# Receiver_1_5.net
KiCad netlist of a schematic drawn in Altium Designer
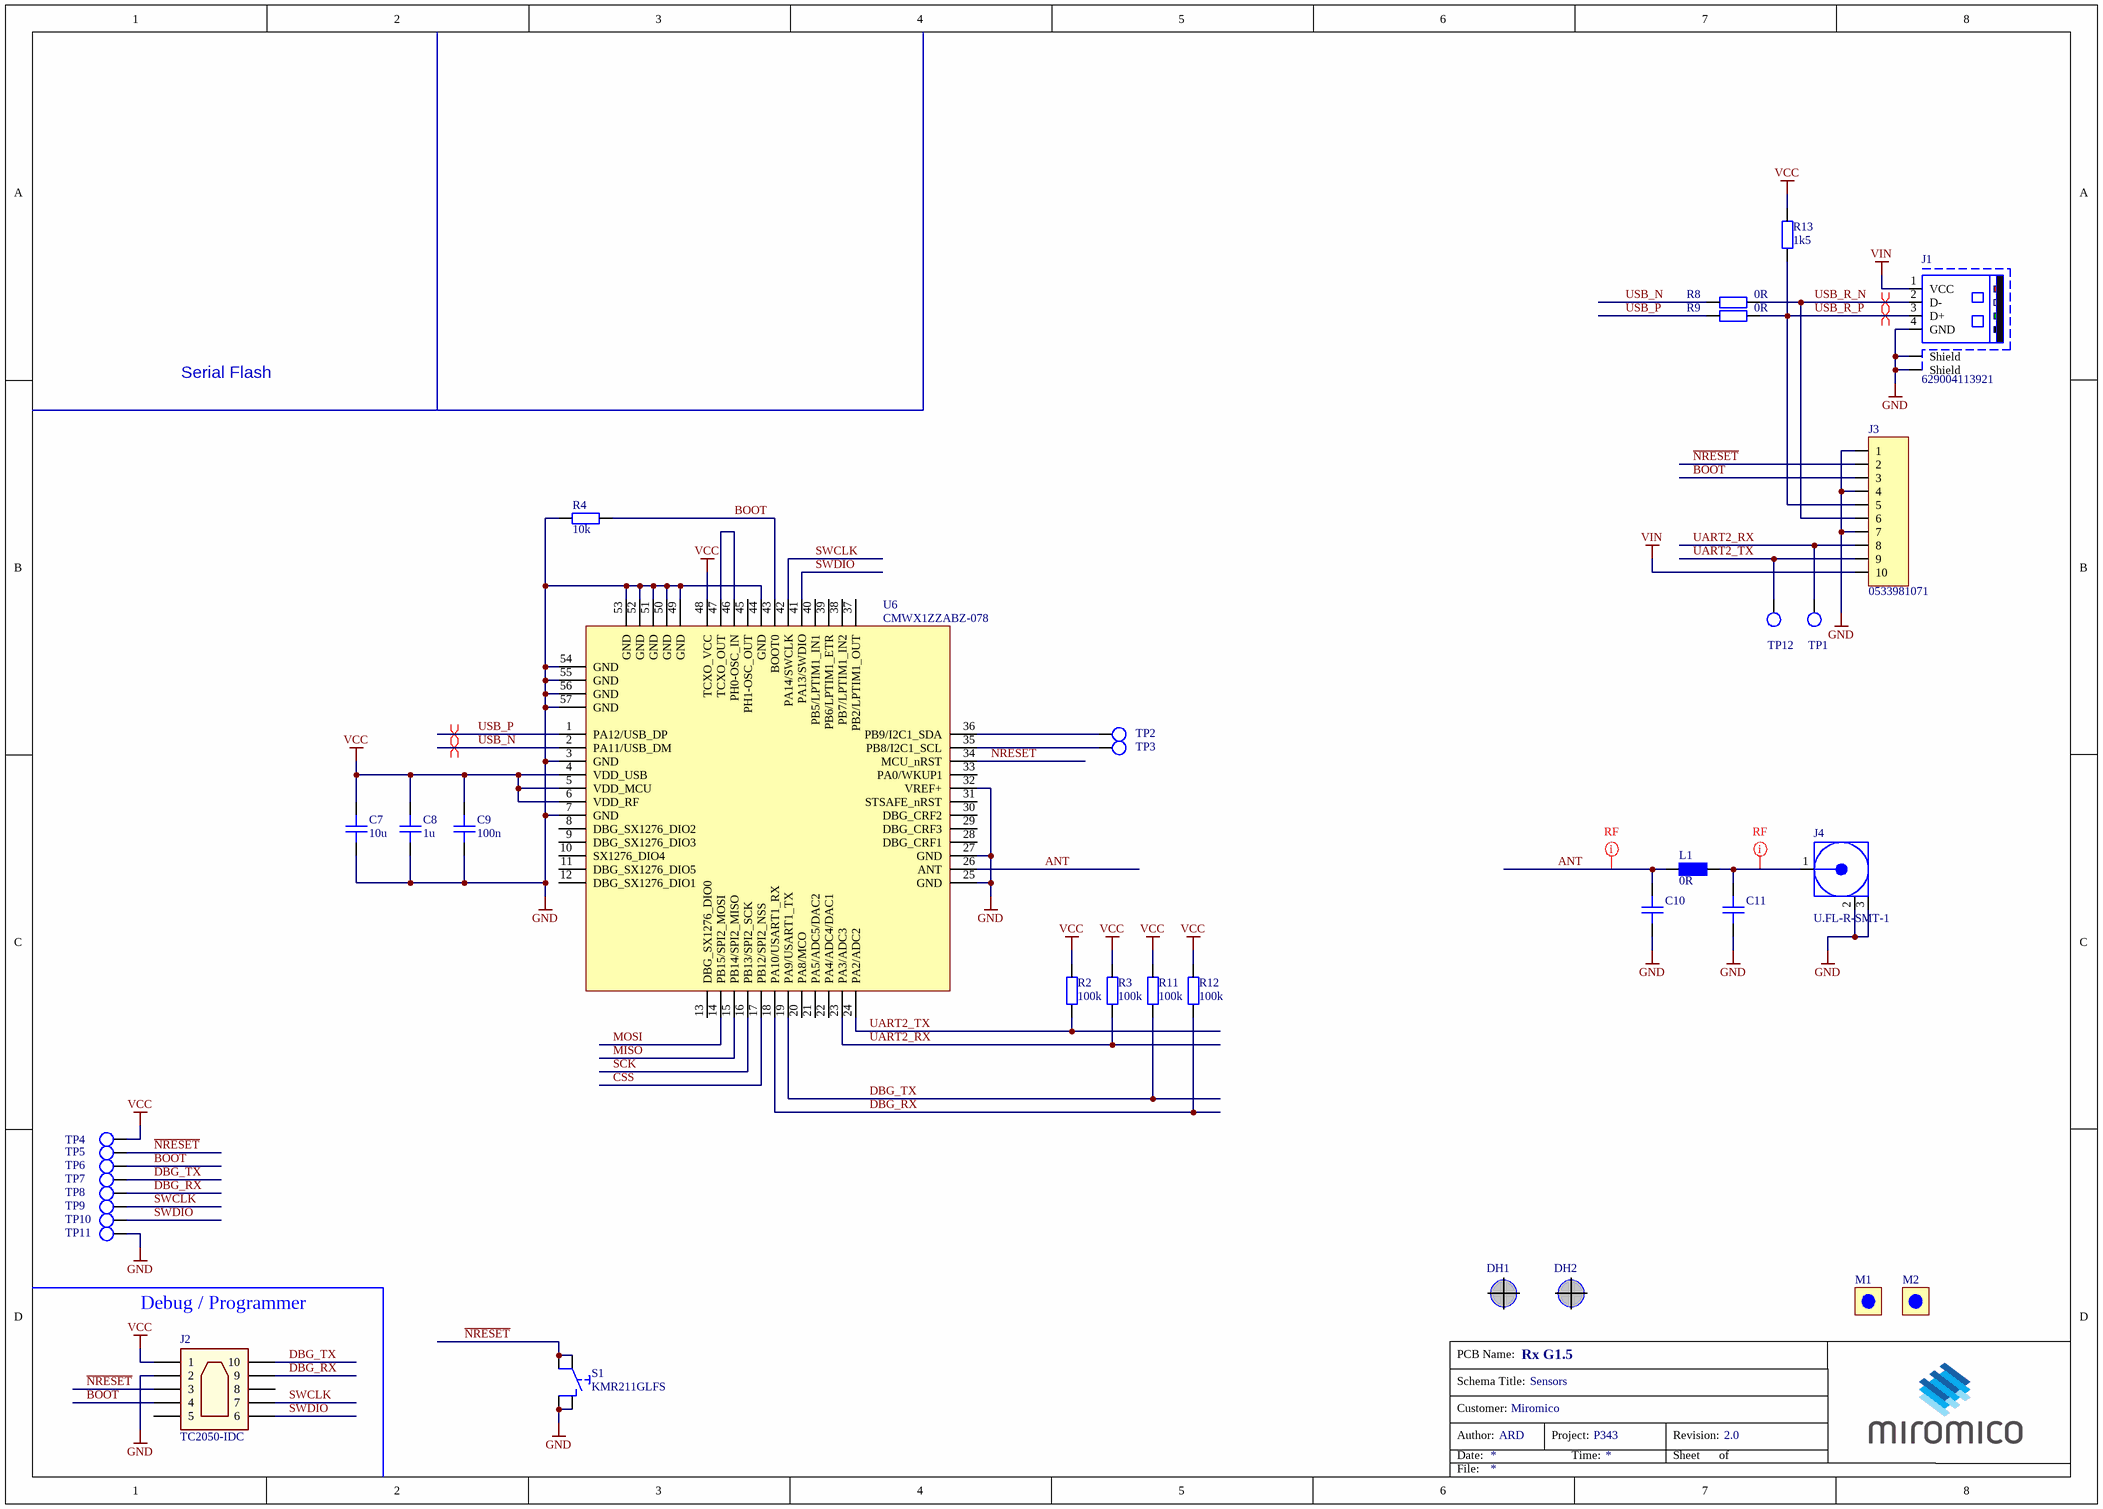
[diagram p0: Receiver_1_5.SchDoc]

(export (version "E")
  (design (tool "Eeschema 10.0.6"))
  (components
    (comp (ref "C7")
      (value "10u")
      (footprint "CAPC0402(1005)60_L")
      (description "Chip Capacitor")
      (libsource (lib "Altium Vault Miromico") (part "C_Chip"))
    )
    (comp (ref "C8")
      (value "1u")
      (footprint "CAPC0402(1005)60_L")
      (description "Chip Capacitor")
      (libsource (lib "Altium Vault Miromico") (part "C_Chip"))
    )
    (comp (ref "C9")
      (value "100n")
      (footprint "CAPC0402(1005)60_L")
      (description "Chip Capacitor")
      (libsource (lib "Altium Vault Miromico") (part "C_Chip"))
    )
    (comp (ref "C10")
      (value "~")
      (footprint "CAPC0402(1005)60_L")
      (description "Chip Capacitor")
      (fields
        (field (name "MANUFACTURER") "Murata Electronics North America")
        (field (name "TOLERANCE") "±0.1pF")
      )
      (libsource (lib "Altium Vault Miromico") (part "C_Chip-03"))
    )
    (comp (ref "C11")
      (value "~")
      (footprint "CAPC0402(1005)60_L")
      (description "Chip Capacitor")
      (fields
        (field (name "MANUFACTURER") "Murata Electronics North America")
        (field (name "TOLERANCE") "±0.1pF")
      )
      (libsource (lib "Altium Vault Miromico") (part "C_Chip-03"))
    )
    (comp (ref "DH1")
      (value "Drill hole M2.5_nonplated")
      (footprint "Drill hole M2.5_nonplated")
      (libsource (lib "Altium Vault Miromico") (part "Drill hole M2.5_nonplated-01"))
    )
    (comp (ref "DH2")
      (value "Drill hole M2.5_nonplated")
      (footprint "Drill hole M2.5_nonplated")
      (libsource (lib "Altium Vault Miromico") (part "Drill hole M2.5_nonplated-01"))
    )
    (comp (ref "J1")
      (value "629004113921")
      (footprint "629004113921")
      (description "WR-COM USB Type A SMT with Clip")
      (fields (field (name "MANUFACTURER") "Wurth Electronics Inc"))
      (libsource (lib "Altium Vault Miromico") (part "629004113921-01"))
    )
    (comp (ref "J2")
      (value "TC2050-IDC")
      (footprint "TC2050-IDC-NL-10")
      (description "TDC2050-IDC, 10Pins, dual footprint (leg and no-legs)")
      (fields (field (name "MANUFACTURER") "Tag-Connect"))
      (libsource (lib "Altium Vault Miromico") (part "TDC2050-IDC-01"))
    )
    (comp (ref "J3")
      (value "0533981071")
      (footprint "0533981071")
      (description "CONN HEADER 10POS 1.25MM VRT SMD")
      (fields (field (name "MANUFACTURER") "Molex, LLC"))
      (libsource (lib "Altium Vault Miromico") (part "0533981071"))
    )
    (comp (ref "J4")
      (value "U.FL-R-SMT-1")
      (footprint "U.FL")
      (description "Ultra Small Surface Mount Coaxial Connectors")
      (fields
        (field (name "MANUFACTURER") "Hirose Electric Co Ltd")
        (field (name "PLACETEC PART NUMBER") "182-916100000000")
      )
      (libsource (lib "Connectors") (part "COAX - U.FL-R-SMT-1"))
    )
    (comp (ref "L1")
      (value "0R")
      (footprint "L_0402_HF")
      (description "Chip Inductor")
      (fields (field (name "TOLERANCE") "±1%"))
      (libsource (lib "Altium Vault Miromico") (part "L_Chip_0402_HF-01"))
    )
    (comp (ref "M1")
      (value "Fiducial Round")
      (footprint "Fiducial round_small")
      (description "Fiducial (Optical Marker)")
      (libsource (lib "Altium Vault Miromico") (part "Fiducial Round-04"))
    )
    (comp (ref "M2")
      (value "Fiducial Round")
      (footprint "Fiducial round_small")
      (description "Fiducial (Optical Marker)")
      (libsource (lib "Altium Vault Miromico") (part "Fiducial Round-04"))
    )
    (comp (ref "R2")
      (value "100k")
      (footprint "RESC0402(1005)_L")
      (description "Chip Resistor")
      (libsource (lib "Altium Vault Miromico") (part "R_Chip"))
    )
    (comp (ref "R3")
      (value "100k")
      (footprint "RESC0402(1005)_L")
      (description "Chip Resistor")
      (libsource (lib "Altium Vault Miromico") (part "R_Chip"))
    )
    (comp (ref "R4")
      (value "10k")
      (footprint "RESC0402(1005)_L")
      (description "Chip Resistor")
      (libsource (lib "") (part "R_Chip-05_1"))
    )
    (comp (ref "R8")
      (value "0R")
      (footprint "RESC0402(1005)_L")
      (description "Chip Resistor")
      (libsource (lib "Altium Vault Miromico") (part "R_Chip-05"))
    )
    (comp (ref "R9")
      (value "0R")
      (footprint "RESC0402(1005)_L")
      (description "Chip Resistor")
      (libsource (lib "Altium Vault Miromico") (part "R_Chip-05"))
    )
    (comp (ref "R11")
      (value "100k")
      (footprint "RESC0402(1005)_L")
      (description "Chip Resistor")
      (libsource (lib "Altium Vault Miromico") (part "R_Chip"))
    )
    (comp (ref "R12")
      (value "100k")
      (footprint "RESC0402(1005)_L")
      (description "Chip Resistor")
      (libsource (lib "Altium Vault Miromico") (part "R_Chip"))
    )
    (comp (ref "R13")
      (value "1k5")
      (footprint "RESC0402(1005)_L")
      (description "Chip Resistor")
      (libsource (lib "Altium Vault Miromico") (part "R_Chip-02"))
    )
    (comp (ref "S1")
      (value "KMR211GLFS")
      (footprint "KMR211GLFS")
      (description "SWITCH TACTILE SPST-NO 0.05A 32V")
      (fields (field (name "MANUFACTURER") "C&K Components"))
      (libsource (lib "Altium Vault Miromico") (part "KMR211GLFS-01"))
    )
    (comp (ref "TP1")
      (value "Testpoint 1.5mm")
      (footprint "Testpoint SMD 1.5mm")
      (description "Testpoint SMD 1.5mm")
      (libsource (lib "Altium Vault Miromico") (part "Testpoint SMD 1.5mm-02"))
    )
    (comp (ref "TP2")
      (value "Testpoint 1.5mm")
      (footprint "Testpoint SMD 1.5mm")
      (description "Testpoint SMD 1.5mm")
      (libsource (lib "Altium Vault Miromico") (part "Testpoint SMD 1.5mm-02"))
    )
    (comp (ref "TP3")
      (value "Testpoint 1.5mm")
      (footprint "Testpoint SMD 1.5mm")
      (description "Testpoint SMD 1.5mm")
      (libsource (lib "Altium Vault Miromico") (part "Testpoint SMD 1.5mm-02"))
    )
    (comp (ref "TP4")
      (value "Testpoint 1.5mm")
      (footprint "Testpoint SMD 1.5mm")
      (description "Testpoint SMD 1.5mm")
      (libsource (lib "Altium Vault Miromico") (part "Testpoint SMD 1.5mm-02"))
    )
    (comp (ref "TP5")
      (value "Testpoint 1.5mm")
      (footprint "Testpoint SMD 1.5mm")
      (description "Testpoint SMD 1.5mm")
      (libsource (lib "Altium Vault Miromico") (part "Testpoint SMD 1.5mm-02"))
    )
    (comp (ref "TP6")
      (value "Testpoint 1.5mm")
      (footprint "Testpoint SMD 1.5mm")
      (description "Testpoint SMD 1.5mm")
      (libsource (lib "Altium Vault Miromico") (part "Testpoint SMD 1.5mm-02"))
    )
    (comp (ref "TP7")
      (value "Testpoint 1.5mm")
      (footprint "Testpoint SMD 1.5mm")
      (description "Testpoint SMD 1.5mm")
      (libsource (lib "Altium Vault Miromico") (part "Testpoint SMD 1.5mm-02"))
    )
    (comp (ref "TP8")
      (value "Testpoint 1.5mm")
      (footprint "Testpoint SMD 1.5mm")
      (description "Testpoint SMD 1.5mm")
      (libsource (lib "Altium Vault Miromico") (part "Testpoint SMD 1.5mm-02"))
    )
    (comp (ref "TP9")
      (value "Testpoint 1.5mm")
      (footprint "Testpoint SMD 1.5mm")
      (description "Testpoint SMD 1.5mm")
      (libsource (lib "Altium Vault Miromico") (part "Testpoint SMD 1.5mm-02"))
    )
    (comp (ref "TP10")
      (value "Testpoint 1.5mm")
      (footprint "Testpoint SMD 1.5mm")
      (description "Testpoint SMD 1.5mm")
      (libsource (lib "Altium Vault Miromico") (part "Testpoint SMD 1.5mm-02"))
    )
    (comp (ref "TP11")
      (value "Testpoint 1.5mm")
      (footprint "Testpoint SMD 1.5mm")
      (description "Testpoint SMD 1.5mm")
      (libsource (lib "Altium Vault Miromico") (part "Testpoint SMD 1.5mm-02"))
    )
    (comp (ref "TP12")
      (value "Testpoint 1.5mm")
      (footprint "Testpoint SMD 1.5mm")
      (description "Testpoint SMD 1.5mm")
      (libsource (lib "Altium Vault Miromico") (part "Testpoint SMD 1.5mm-02"))
    )
    (comp (ref "U6")
      (value "CMWX1ZZABZ-078")
      (footprint "CMWX1ZZABZ")
      (description "LORA MODULE")
      (fields (field (name "MANUFACTURER") "Murata Electronics North America"))
      (libsource (lib "CMWX1ZZABZ") (part "CMWX1ZZABZ-078"))
    )
  )
  (nets
    (net (code "1") (name "/ANT") (class "Default")
      (node (ref "C10") (pin "1") (pinfunction "1_1") (pintype "passive"))
      (node (ref "L1") (pin "2") (pinfunction "2_2") (pintype "passive"))
      (node (ref "U6") (pin "26") (pinfunction "ANT_26") (pintype "passive"))
    )
    (net (code "2") (name "/BOOT") (class "Default")
      (node (ref "J2") (pin "4") (pinfunction "4_4") (pintype "passive"))
      (node (ref "J3") (pin "3") (pinfunction "3_3") (pintype "passive"))
      (node (ref "R4") (pin "1") (pinfunction "1_1") (pintype "passive"))
      (node (ref "TP6") (pin "1") (pinfunction "1_1") (pintype "passive"))
      (node (ref "U6") (pin "43") (pinfunction "BOOT0_43") (pintype "passive"))
    )
    (net (code "3") (name "/CSS") (class "Default")
      (node (ref "U6") (pin "17") (pinfunction "PB12/SPI2_NSS_17") (pintype "passive"))
    )
    (net (code "4") (name "/DBG_RX") (class "Default")
      (node (ref "J2") (pin "9") (pinfunction "9_9") (pintype "passive"))
      (node (ref "R12") (pin "2") (pinfunction "2_2") (pintype "passive"))
      (node (ref "TP8") (pin "1") (pinfunction "1_1") (pintype "passive"))
      (node (ref "U6") (pin "18") (pinfunction "PA10/USART1_RX_18") (pintype "passive"))
    )
    (net (code "5") (name "/DBG_TX") (class "Default")
      (node (ref "J2") (pin "10") (pinfunction "10_10") (pintype "passive"))
      (node (ref "R11") (pin "2") (pinfunction "2_2") (pintype "passive"))
      (node (ref "TP7") (pin "1") (pinfunction "1_1") (pintype "passive"))
      (node (ref "U6") (pin "19") (pinfunction "PA9/USART1_TX_19") (pintype "passive"))
    )
    (net (code "6") (name "/MISO") (class "Default")
      (node (ref "U6") (pin "15") (pinfunction "PB14/SPI2_MISO_15") (pintype "passive"))
    )
    (net (code "7") (name "/MOSI") (class "Default")
      (node (ref "U6") (pin "14") (pinfunction "PB15/SPI2_MOSI_14") (pintype "passive"))
    )
    (net (code "8") (name "/NRESET") (class "Default")
      (node (ref "J2") (pin "3") (pinfunction "3_3") (pintype "passive"))
      (node (ref "J3") (pin "2") (pinfunction "2_2") (pintype "passive"))
      (node (ref "S1") (pin "1") (pinfunction "1_1") (pintype "passive"))
      (node (ref "S1") (pin "2") (pinfunction "2_2") (pintype "passive"))
      (node (ref "TP5") (pin "1") (pinfunction "1_1") (pintype "passive"))
      (node (ref "U6") (pin "34") (pinfunction "MCU_nRST_34") (pintype "passive"))
    )
    (net (code "9") (name "/SCK") (class "Default")
      (node (ref "U6") (pin "16") (pinfunction "PB13/SPI2_SCK_16") (pintype "passive"))
    )
    (net (code "10") (name "/SWCLK") (class "Default")
      (node (ref "J2") (pin "7") (pinfunction "7_7") (pintype "passive"))
      (node (ref "TP9") (pin "1") (pinfunction "1_1") (pintype "passive"))
      (node (ref "U6") (pin "42") (pinfunction "PA14/SWCLK_42") (pintype "passive"))
    )
    (net (code "11") (name "/SWDIO") (class "Default")
      (node (ref "J2") (pin "6") (pinfunction "6_6") (pintype "passive"))
      (node (ref "TP10") (pin "1") (pinfunction "1_1") (pintype "passive"))
      (node (ref "U6") (pin "41") (pinfunction "PA13/SWDIO_41") (pintype "passive"))
    )
    (net (code "12") (name "/UART2_RX") (class "Default")
      (node (ref "J3") (pin "8") (pinfunction "8_8") (pintype "passive"))
      (node (ref "R3") (pin "2") (pinfunction "2_2") (pintype "passive"))
      (node (ref "TP1") (pin "1") (pinfunction "1_1") (pintype "passive"))
      (node (ref "U6") (pin "23") (pinfunction "PA3/ADC3_23") (pintype "passive"))
    )
    (net (code "13") (name "/UART2_TX") (class "Default")
      (node (ref "J3") (pin "9") (pinfunction "9_9") (pintype "passive"))
      (node (ref "R2") (pin "2") (pinfunction "2_2") (pintype "passive"))
      (node (ref "TP12") (pin "1") (pinfunction "1_1") (pintype "passive"))
      (node (ref "U6") (pin "24") (pinfunction "PA2/ADC2_24") (pintype "passive"))
    )
    (net (code "14") (name "/USB_N") (class "Default")
      (node (ref "R8") (pin "1") (pinfunction "1_1") (pintype "passive"))
      (node (ref "U6") (pin "2") (pinfunction "PA11/USB_DM_2") (pintype "passive"))
    )
    (net (code "15") (name "/USB_P") (class "Default")
      (node (ref "R9") (pin "1") (pinfunction "1_1") (pintype "passive"))
      (node (ref "U6") (pin "1") (pinfunction "PA12/USB_DP_1") (pintype "passive"))
    )
    (net (code "16") (name "/USB_R_N") (class "Default")
      (node (ref "J1") (pin "2") (pinfunction "D-_2") (pintype "passive"))
      (node (ref "J3") (pin "6") (pinfunction "6_6") (pintype "passive"))
      (node (ref "R8") (pin "2") (pinfunction "2_2") (pintype "passive"))
    )
    (net (code "17") (name "/USB_R_P") (class "Default")
      (node (ref "J1") (pin "3") (pinfunction "D+_3") (pintype "passive"))
      (node (ref "J3") (pin "5") (pinfunction "5_5") (pintype "passive"))
      (node (ref "R13") (pin "2") (pinfunction "2_2") (pintype "passive"))
      (node (ref "R9") (pin "2") (pinfunction "2_2") (pintype "passive"))
    )
    (net (code "18") (name "GND") (class "Default")
      (node (ref "C10") (pin "2") (pinfunction "2_2") (pintype "passive"))
      (node (ref "C11") (pin "2") (pinfunction "2_2") (pintype "passive"))
      (node (ref "C7") (pin "1") (pinfunction "1_1") (pintype "passive"))
      (node (ref "C8") (pin "1") (pinfunction "1_1") (pintype "passive"))
      (node (ref "C9") (pin "1") (pinfunction "1_1") (pintype "passive"))
      (node (ref "J1") (pin "4") (pinfunction "GND_4") (pintype "passive"))
      (node (ref "J1") (pin "Z1") (pinfunction "Shield_Z1") (pintype "passive"))
      (node (ref "J1") (pin "Z2") (pinfunction "Shield_Z2") (pintype "passive"))
      (node (ref "J2") (pin "2") (pinfunction "2_2") (pintype "passive"))
      (node (ref "J3") (pin "1") (pinfunction "1_1") (pintype "passive"))
      (node (ref "J3") (pin "4") (pinfunction "4_4") (pintype "passive"))
      (node (ref "J3") (pin "7") (pinfunction "7_7") (pintype "passive"))
      (node (ref "J4") (pin "2") (pinfunction "GND_2") (pintype "power_in"))
      (node (ref "J4") (pin "3") (pinfunction "GND_3") (pintype "power_in"))
      (node (ref "R4") (pin "2") (pinfunction "2_2") (pintype "passive"))
      (node (ref "S1") (pin "3") (pinfunction "3_3") (pintype "passive"))
      (node (ref "S1") (pin "4") (pinfunction "4_4") (pintype "passive"))
      (node (ref "TP11") (pin "1") (pinfunction "1_1") (pintype "passive"))
      (node (ref "U6") (pin "25") (pinfunction "GND_25") (pintype "passive"))
      (node (ref "U6") (pin "27") (pinfunction "GND_27") (pintype "passive"))
      (node (ref "U6") (pin "3") (pinfunction "GND_3") (pintype "passive"))
      (node (ref "U6") (pin "32") (pinfunction "VREF+_32") (pintype "passive"))
      (node (ref "U6") (pin "44") (pinfunction "GND_44") (pintype "passive"))
      (node (ref "U6") (pin "49") (pinfunction "GND_49") (pintype "passive"))
      (node (ref "U6") (pin "50") (pinfunction "GND_50") (pintype "passive"))
      (node (ref "U6") (pin "51") (pinfunction "GND_51") (pintype "passive"))
      (node (ref "U6") (pin "52") (pinfunction "GND_52") (pintype "passive"))
      (node (ref "U6") (pin "53") (pinfunction "GND_53") (pintype "passive"))
      (node (ref "U6") (pin "54") (pinfunction "GND_54") (pintype "passive"))
      (node (ref "U6") (pin "55") (pinfunction "GND_55") (pintype "passive"))
      (node (ref "U6") (pin "56") (pinfunction "GND_56") (pintype "passive"))
      (node (ref "U6") (pin "57") (pinfunction "GND_57") (pintype "passive"))
      (node (ref "U6") (pin "7") (pinfunction "GND_7") (pintype "passive"))
    )
    (net (code "19") (name "Net-(J4-Signal)") (class "Default")
      (node (ref "C11") (pin "1") (pinfunction "1_1") (pintype "passive"))
      (node (ref "J4") (pin "1") (pinfunction "Signal_1") (pintype "passive"))
      (node (ref "L1") (pin "1") (pinfunction "1_1") (pintype "passive"))
    )
    (net (code "20") (name "Net-(U6-PB8{slash}I2C1_SCL)") (class "Default")
      (node (ref "TP3") (pin "1") (pinfunction "1_1") (pintype "passive"))
      (node (ref "U6") (pin "35") (pinfunction "PB8/I2C1_SCL_35") (pintype "passive"))
    )
    (net (code "21") (name "Net-(U6-PB9{slash}I2C1_SDA)") (class "Default")
      (node (ref "TP2") (pin "1") (pinfunction "1_1") (pintype "passive"))
      (node (ref "U6") (pin "36") (pinfunction "PB9/I2C1_SDA_36") (pintype "passive"))
    )
    (net (code "22") (name "Net-(U6-PH0-OSC_IN)") (class "Default")
      (node (ref "U6") (pin "46") (pinfunction "PH0-OSC_IN_46") (pintype "passive"))
      (node (ref "U6") (pin "47") (pinfunction "TCXO_OUT_47") (pintype "passive"))
    )
    (net (code "23") (name "VCC") (class "Default")
      (node (ref "C7") (pin "2") (pinfunction "2_2") (pintype "passive"))
      (node (ref "C8") (pin "2") (pinfunction "2_2") (pintype "passive"))
      (node (ref "C9") (pin "2") (pinfunction "2_2") (pintype "passive"))
      (node (ref "J2") (pin "1") (pinfunction "1_1") (pintype "passive"))
      (node (ref "R11") (pin "1") (pinfunction "1_1") (pintype "passive"))
      (node (ref "R12") (pin "1") (pinfunction "1_1") (pintype "passive"))
      (node (ref "R13") (pin "1") (pinfunction "1_1") (pintype "passive"))
      (node (ref "R2") (pin "1") (pinfunction "1_1") (pintype "passive"))
      (node (ref "R3") (pin "1") (pinfunction "1_1") (pintype "passive"))
      (node (ref "TP4") (pin "1") (pinfunction "1_1") (pintype "passive"))
      (node (ref "U6") (pin "4") (pinfunction "VDD_USB_4") (pintype "passive"))
      (node (ref "U6") (pin "48") (pinfunction "TCXO_VCC_48") (pintype "passive"))
      (node (ref "U6") (pin "5") (pinfunction "VDD_MCU_5") (pintype "passive"))
      (node (ref "U6") (pin "6") (pinfunction "VDD_RF_6") (pintype "passive"))
    )
    (net (code "24") (name "VIN") (class "Default")
      (node (ref "J1") (pin "1") (pinfunction "VCC_1") (pintype "passive"))
      (node (ref "J3") (pin "10") (pinfunction "10_10") (pintype "passive"))
    )
    (net (code "25") (name "unconnected-(J2-Pad5)") (class "Default")
      (node (ref "J2") (pin "5") (pinfunction "5_5") (pintype "passive"))
    )
    (net (code "26") (name "unconnected-(J2-Pad8)") (class "Default")
      (node (ref "J2") (pin "8") (pinfunction "8_8") (pintype "passive"))
    )
    (net (code "27") (name "unconnected-(U6-DBG_CRF1-Pad28)") (class "Default")
      (node (ref "U6") (pin "28") (pinfunction "DBG_CRF1_28") (pintype "passive"))
    )
    (net (code "28") (name "unconnected-(U6-DBG_CRF2-Pad30)") (class "Default")
      (node (ref "U6") (pin "30") (pinfunction "DBG_CRF2_30") (pintype "passive"))
    )
    (net (code "29") (name "unconnected-(U6-DBG_CRF3-Pad29)") (class "Default")
      (node (ref "U6") (pin "29") (pinfunction "DBG_CRF3_29") (pintype "passive"))
    )
    (net (code "30") (name "unconnected-(U6-DBG_SX1276_DIO0-Pad13)") (class "Default")
      (node (ref "U6") (pin "13") (pinfunction "DBG_SX1276_DIO0_13") (pintype "passive"))
    )
    (net (code "31") (name "unconnected-(U6-DBG_SX1276_DIO1-Pad12)") (class "Default")
      (node (ref "U6") (pin "12") (pinfunction "DBG_SX1276_DIO1_12") (pintype "passive"))
    )
    (net (code "32") (name "unconnected-(U6-DBG_SX1276_DIO2-Pad8)") (class "Default")
      (node (ref "U6") (pin "8") (pinfunction "DBG_SX1276_DIO2_8") (pintype "passive"))
    )
    (net (code "33") (name "unconnected-(U6-DBG_SX1276_DIO3-Pad9)") (class "Default")
      (node (ref "U6") (pin "9") (pinfunction "DBG_SX1276_DIO3_9") (pintype "passive"))
    )
    (net (code "34") (name "unconnected-(U6-DBG_SX1276_DIO5-Pad11)") (class "Default")
      (node (ref "U6") (pin "11") (pinfunction "DBG_SX1276_DIO5_11") (pintype "passive"))
    )
    (net (code "35") (name "unconnected-(U6-PA0{slash}WKUP1-Pad33)") (class "Default")
      (node (ref "U6") (pin "33") (pinfunction "PA0/WKUP1_33") (pintype "passive"))
    )
    (net (code "36") (name "unconnected-(U6-PA4{slash}ADC4{slash}DAC1-Pad22)") (class "Default")
      (node (ref "U6") (pin "22") (pinfunction "PA4/ADC4/DAC1_22") (pintype "passive"))
    )
    (net (code "37") (name "unconnected-(U6-PA5{slash}ADC5{slash}DAC2-Pad21)") (class "Default")
      (node (ref "U6") (pin "21") (pinfunction "PA5/ADC5/DAC2_21") (pintype "passive"))
    )
    (net (code "38") (name "unconnected-(U6-PA8{slash}MCO-Pad20)") (class "Default")
      (node (ref "U6") (pin "20") (pinfunction "PA8/MCO_20") (pintype "passive"))
    )
    (net (code "39") (name "unconnected-(U6-PB2{slash}LPTIM1_OUT-Pad37)") (class "Default")
      (node (ref "U6") (pin "37") (pinfunction "PB2/LPTIM1_OUT_37") (pintype "passive"))
    )
    (net (code "40") (name "unconnected-(U6-PB5{slash}LPTIM1_IN1-Pad40)") (class "Default")
      (node (ref "U6") (pin "40") (pinfunction "PB5/LPTIM1_IN1_40") (pintype "passive"))
    )
    (net (code "41") (name "unconnected-(U6-PB6{slash}LPTIM1_ETR-Pad39)") (class "Default")
      (node (ref "U6") (pin "39") (pinfunction "PB6/LPTIM1_ETR_39") (pintype "passive"))
    )
    (net (code "42") (name "unconnected-(U6-PB7{slash}LPTIM1_IN2-Pad38)") (class "Default")
      (node (ref "U6") (pin "38") (pinfunction "PB7/LPTIM1_IN2_38") (pintype "passive"))
    )
    (net (code "43") (name "unconnected-(U6-PH1-OSC_OUT-Pad45)") (class "Default")
      (node (ref "U6") (pin "45") (pinfunction "PH1-OSC_OUT_45") (pintype "passive"))
    )
    (net (code "44") (name "unconnected-(U6-STSAFE_nRST-Pad31)") (class "Default")
      (node (ref "U6") (pin "31") (pinfunction "STSAFE_nRST_31") (pintype "passive"))
    )
    (net (code "45") (name "unconnected-(U6-SX1276_DIO4-Pad10)") (class "Default")
      (node (ref "U6") (pin "10") (pinfunction "SX1276_DIO4_10") (pintype "passive"))
    )
  )
)
